# isolator2_0.net
KiCad netlist of a schematic drawn in EAGLE
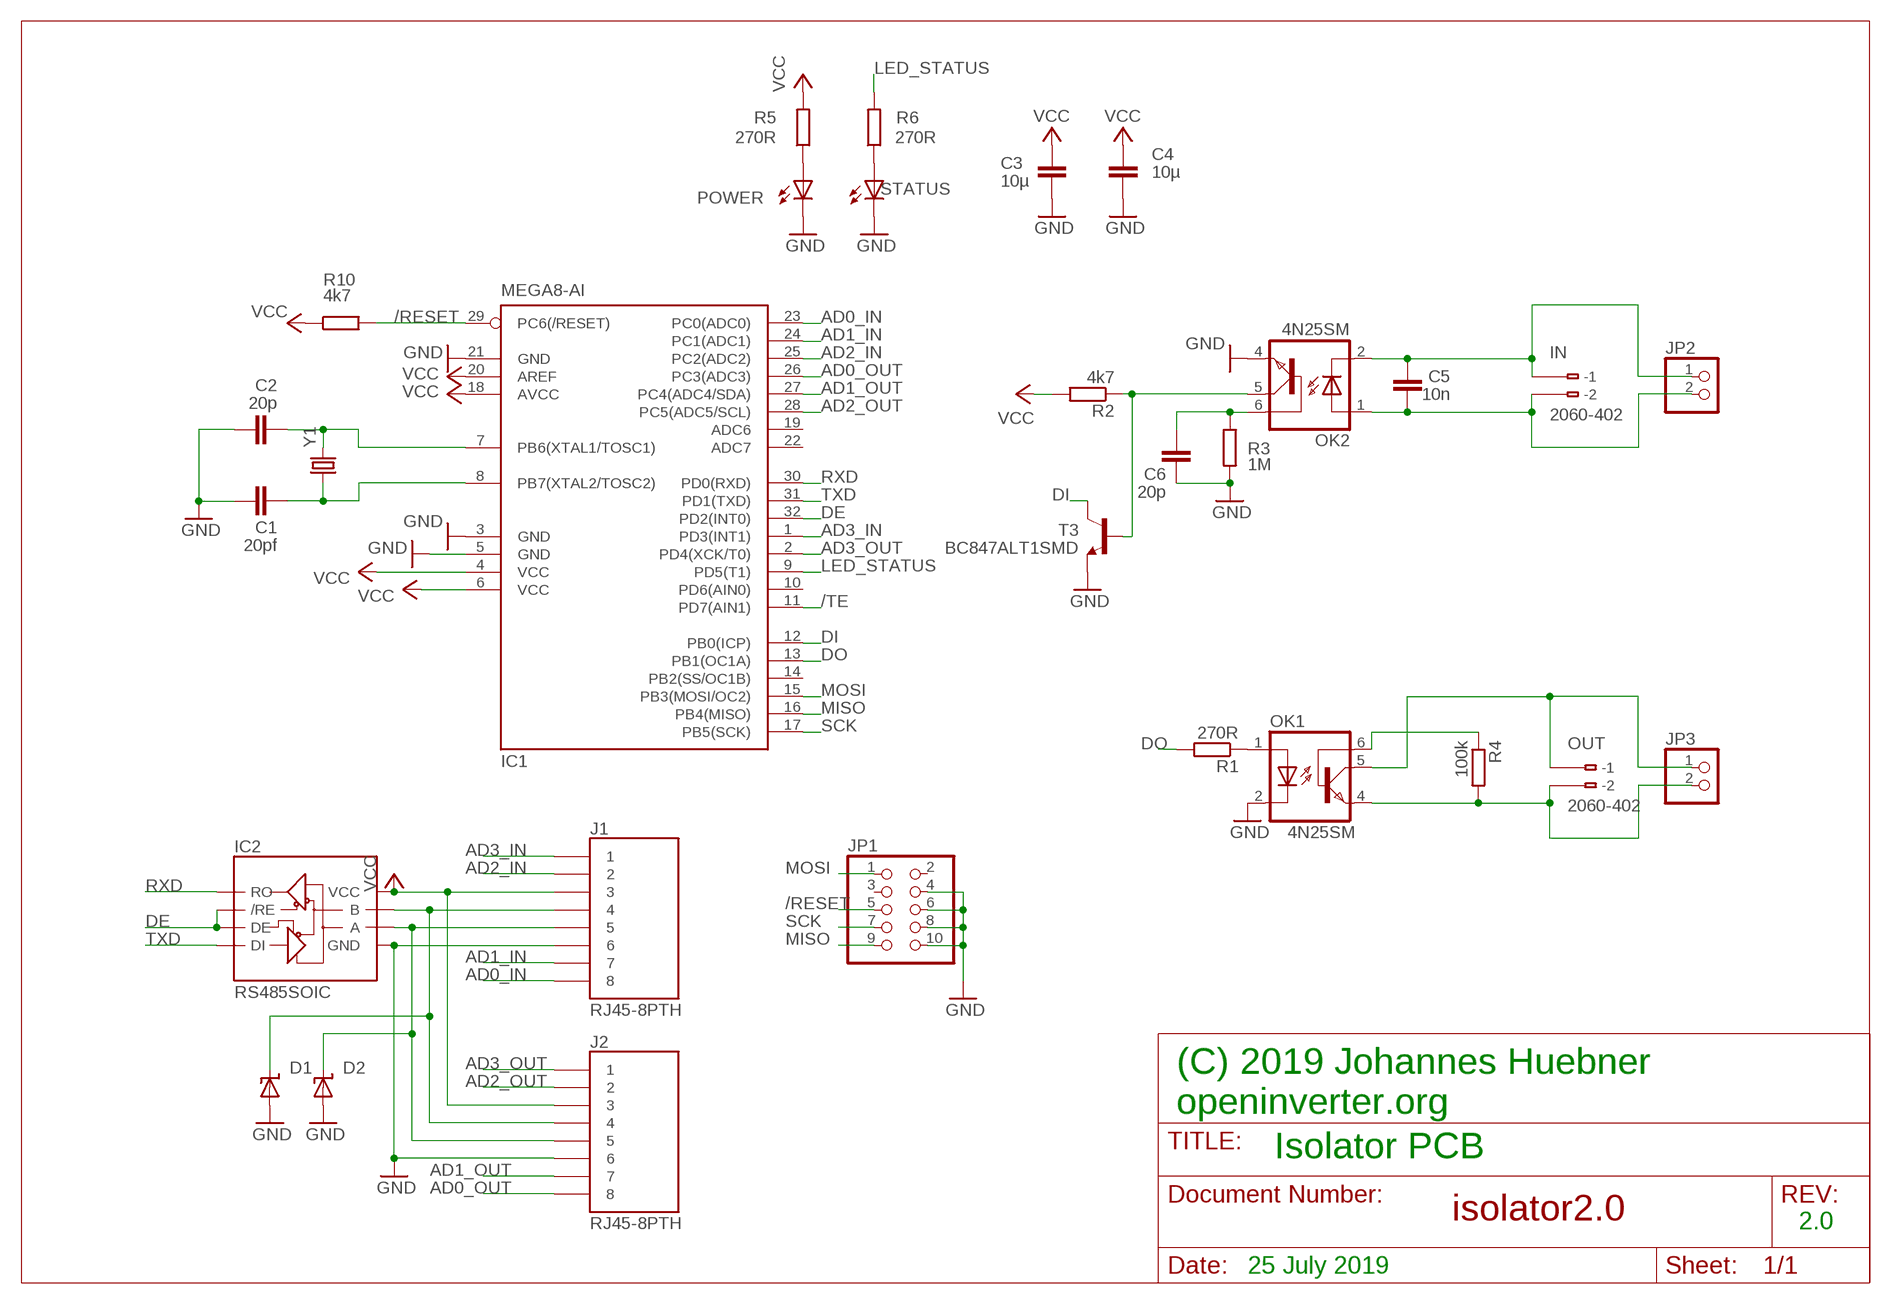
[diagram p0: schematic, sheet 1]

(export (version "E")
  (design (tool "Eeschema 10.0.6"))
  (components
    (comp (ref "C1")
      (value "20pf")
      (footprint "eagle-import:C0805")
      (libsource (lib "eagle-import") (part "C-EUC0805"))
    )
    (comp (ref "C2")
      (value "20p")
      (footprint "eagle-import:C0805")
      (libsource (lib "eagle-import") (part "C-EUC0805"))
    )
    (comp (ref "C3")
      (value "10µ")
      (footprint "eagle-import:C0805")
      (libsource (lib "eagle-import") (part "C-EUC0805"))
    )
    (comp (ref "C4")
      (value "10µ")
      (footprint "eagle-import:C0805")
      (libsource (lib "eagle-import") (part "C-EUC0805"))
    )
    (comp (ref "C5")
      (value "10n")
      (footprint "eagle-import:C0805")
      (libsource (lib "eagle-import") (part "C-EUC0805"))
    )
    (comp (ref "C6")
      (value "20p")
      (footprint "eagle-import:C0805")
      (libsource (lib "eagle-import") (part "C-EUC0805"))
    )
    (comp (ref "D1")
      (value "SUPPRESSOR-SMBJ")
      (footprint "eagle-import:SMBJ")
      (libsource (lib "eagle-import") (part "SUPPRESSOR-SMBJ"))
    )
    (comp (ref "D2")
      (value "SUPPRESSOR-SMBJ")
      (footprint "eagle-import:SMBJ")
      (libsource (lib "eagle-import") (part "SUPPRESSOR-SMBJ"))
    )
    (comp (ref "IC1")
      (value "MEGA8-AI")
      (footprint "eagle-import:TQFP32-08")
      (fields (field (name "MPN") "ATMEGA8-16AU"))
      (libsource (lib "eagle-import") (part "MEGA8-AI"))
    )
    (comp (ref "IC2")
      (value "RS485SOIC")
      (footprint "eagle-import:SO08")
      (libsource (lib "eagle-import") (part "RS485SOIC"))
    )
    (comp (ref "IN")
      (value "2060-402")
      (footprint "eagle-import:2060-402")
      (libsource (lib "eagle-import") (part "2060-402"))
    )
    (comp (ref "J1")
      (value "RJ45-8PTH")
      (footprint "eagle-import:RJ45-8")
      (libsource (lib "eagle-import") (part "RJ45-8PTH"))
    )
    (comp (ref "J2")
      (value "RJ45-8PTH")
      (footprint "eagle-import:RJ45-8")
      (libsource (lib "eagle-import") (part "RJ45-8PTH"))
    )
    (comp (ref "JP1")
      (value "PINHD-2X5")
      (footprint "eagle-import:2X05")
      (libsource (lib "eagle-import") (part "PINHD-2X5"))
    )
    (comp (ref "JP2")
      (value "PINHD-1X2")
      (footprint "eagle-import:1X02")
      (libsource (lib "eagle-import") (part "PINHD-1X2"))
    )
    (comp (ref "JP3")
      (value "PINHD-1X2")
      (footprint "eagle-import:1X02")
      (libsource (lib "eagle-import") (part "PINHD-1X2"))
    )
    (comp (ref "OK1")
      (value "4N25SM")
      (footprint "eagle-import:DIL6-SMD")
      (fields (field (name "MF") "FAIRCHILD SEMICONDUCTOR"))
      (libsource (lib "eagle-import") (part "4N?MS25"))
    )
    (comp (ref "OK2")
      (value "4N25SM")
      (footprint "eagle-import:DIL6-SMD")
      (fields (field (name "MF") "FAIRCHILD SEMICONDUCTOR"))
      (libsource (lib "eagle-import") (part "4N?MS25"))
    )
    (comp (ref "OUT")
      (value "2060-402")
      (footprint "eagle-import:2060-402")
      (libsource (lib "eagle-import") (part "2060-402"))
    )
    (comp (ref "POWER")
      (value "LEDCHIP-LED0805")
      (footprint "eagle-import:CHIP-LED0805")
      (libsource (lib "eagle-import") (part "LEDCHIP-LED0805"))
    )
    (comp (ref "R1")
      (value "270R")
      (footprint "eagle-import:M0805")
      (libsource (lib "eagle-import") (part "R-EU_M0805"))
    )
    (comp (ref "R2")
      (value "4k7")
      (footprint "eagle-import:M0805")
      (libsource (lib "eagle-import") (part "R-EU_M0805"))
    )
    (comp (ref "R3")
      (value "1M")
      (footprint "eagle-import:M0805")
      (libsource (lib "eagle-import") (part "R-EU_M0805"))
    )
    (comp (ref "R4")
      (value "100k")
      (footprint "eagle-import:M0805")
      (libsource (lib "eagle-import") (part "R-EU_M0805"))
    )
    (comp (ref "R5")
      (value "270R")
      (footprint "eagle-import:M0805")
      (libsource (lib "eagle-import") (part "R-EU_M0805"))
    )
    (comp (ref "R6")
      (value "270R")
      (footprint "eagle-import:M0805")
      (libsource (lib "eagle-import") (part "R-EU_M0805"))
    )
    (comp (ref "R10")
      (value "4k7")
      (footprint "eagle-import:M0805")
      (libsource (lib "eagle-import") (part "R-EU_M0805"))
    )
    (comp (ref "STATUS")
      (value "LEDCHIP-LED0805")
      (footprint "eagle-import:CHIP-LED0805")
      (libsource (lib "eagle-import") (part "LEDCHIP-LED0805"))
    )
    (comp (ref "T3")
      (value "BC847ALT1SMD")
      (footprint "eagle-import:SOT23")
      (libsource (lib "eagle-import") (part "BC847SMDALT1"))
    )
    (comp (ref "Y1")
      (value "CRYSTAL10.5X4.8")
      (footprint "eagle-import:CRYSTAL-SMD-10.5X4.8-2PIN")
      (libsource (lib "eagle-import") (part "CRYSTAL10.5X4.8"))
    )
  )
  (nets
    (net (code "1") (name "/AD0_IN") (class "Default")
      (node (ref "IC1") (pin "23") (pinfunction "PC0(ADC0)_23") (pintype "bidirectional"))
      (node (ref "J1") (pin "8") (pinfunction "8_8") (pintype "bidirectional"))
    )
    (net (code "2") (name "/AD0_OUT") (class "Default")
      (node (ref "IC1") (pin "26") (pinfunction "PC3(ADC3)_26") (pintype "bidirectional"))
      (node (ref "J2") (pin "8") (pinfunction "8_8") (pintype "bidirectional"))
    )
    (net (code "3") (name "/AD1_IN") (class "Default")
      (node (ref "IC1") (pin "24") (pinfunction "PC1(ADC1)_24") (pintype "bidirectional"))
      (node (ref "J1") (pin "7") (pinfunction "7_7") (pintype "bidirectional"))
    )
    (net (code "4") (name "/AD1_OUT") (class "Default")
      (node (ref "IC1") (pin "27") (pinfunction "PC4(ADC4/SDA)_27") (pintype "bidirectional"))
      (node (ref "J2") (pin "7") (pinfunction "7_7") (pintype "bidirectional"))
    )
    (net (code "5") (name "/AD2_IN") (class "Default")
      (node (ref "IC1") (pin "25") (pinfunction "PC2(ADC2)_25") (pintype "bidirectional"))
      (node (ref "J1") (pin "2") (pinfunction "2_2") (pintype "bidirectional"))
    )
    (net (code "6") (name "/AD2_OUT") (class "Default")
      (node (ref "IC1") (pin "28") (pinfunction "PC5(ADC5/SCL)_28") (pintype "bidirectional"))
      (node (ref "J2") (pin "2") (pinfunction "2_2") (pintype "bidirectional"))
    )
    (net (code "7") (name "/AD3_IN") (class "Default")
      (node (ref "IC1") (pin "1") (pinfunction "PD3(INT1)_1") (pintype "bidirectional"))
      (node (ref "J1") (pin "1") (pinfunction "1_1") (pintype "bidirectional"))
    )
    (net (code "8") (name "/AD3_OUT") (class "Default")
      (node (ref "IC1") (pin "2") (pinfunction "PD4(XCK/T0)_2") (pintype "bidirectional"))
      (node (ref "J2") (pin "1") (pinfunction "1_1") (pintype "bidirectional"))
    )
    (net (code "9") (name "/DE") (class "Default")
      (node (ref "IC1") (pin "32") (pinfunction "PD2(INT0)_32") (pintype "bidirectional"))
      (node (ref "IC2") (pin "2") (pinfunction "/RE_2") (pintype "bidirectional"))
      (node (ref "IC2") (pin "3") (pinfunction "DE_3") (pintype "bidirectional"))
    )
    (net (code "10") (name "/DI") (class "Default")
      (node (ref "IC1") (pin "12") (pinfunction "PB0(ICP)_12") (pintype "bidirectional"))
      (node (ref "T3") (pin "3") (pinfunction "C_3") (pintype "passive"))
    )
    (net (code "11") (name "/DO") (class "Default")
      (node (ref "IC1") (pin "13") (pinfunction "PB1(OC1A)_13") (pintype "bidirectional"))
      (node (ref "R1") (pin "2") (pinfunction "2_2") (pintype "passive"))
    )
    (net (code "12") (name "/LED_STATUS") (class "Default")
      (node (ref "IC1") (pin "9") (pinfunction "PD5(T1)_9") (pintype "bidirectional"))
      (node (ref "R6") (pin "2") (pinfunction "2_2") (pintype "passive"))
    )
    (net (code "13") (name "/MISO") (class "Default")
      (node (ref "IC1") (pin "16") (pinfunction "PB4(MISO)_16") (pintype "bidirectional"))
      (node (ref "JP1") (pin "9") (pinfunction "9_9") (pintype "passive"))
    )
    (net (code "14") (name "/MOSI") (class "Default")
      (node (ref "IC1") (pin "15") (pinfunction "PB3(MOSI/OC2)_15") (pintype "bidirectional"))
      (node (ref "JP1") (pin "1") (pinfunction "1_1") (pintype "passive"))
    )
    (net (code "15") (name "/RXD") (class "Default")
      (node (ref "IC1") (pin "30") (pinfunction "PD0(RXD)_30") (pintype "bidirectional"))
      (node (ref "IC2") (pin "1") (pinfunction "RO_1") (pintype "bidirectional"))
    )
    (net (code "16") (name "/SCK") (class "Default")
      (node (ref "IC1") (pin "17") (pinfunction "PB5(SCK)_17") (pintype "bidirectional"))
      (node (ref "JP1") (pin "7") (pinfunction "7_7") (pintype "passive"))
    )
    (net (code "17") (name "/TXD") (class "Default")
      (node (ref "IC1") (pin "31") (pinfunction "PD1(TXD)_31") (pintype "bidirectional"))
      (node (ref "IC2") (pin "4") (pinfunction "DI_4") (pintype "bidirectional"))
    )
    (net (code "18") (name "/{slash}RESET") (class "Default")
      (node (ref "IC1") (pin "29") (pinfunction "PC6(/RESET)_29") (pintype "bidirectional"))
      (node (ref "JP1") (pin "5") (pinfunction "5_5") (pintype "passive"))
      (node (ref "R10") (pin "2") (pinfunction "2_2") (pintype "passive"))
    )
    (net (code "19") (name "/{slash}TE") (class "Default")
      (node (ref "IC1") (pin "11") (pinfunction "PD7(AIN1)_11") (pintype "bidirectional"))
    )
    (net (code "20") (name "GND") (class "Default")
      (node (ref "C1") (pin "1") (pinfunction "1_1") (pintype "passive"))
      (node (ref "C2") (pin "1") (pinfunction "1_1") (pintype "passive"))
      (node (ref "C3") (pin "2") (pinfunction "2_2") (pintype "passive"))
      (node (ref "C4") (pin "2") (pinfunction "2_2") (pintype "passive"))
      (node (ref "C6") (pin "1") (pinfunction "1_1") (pintype "passive"))
      (node (ref "D1") (pin "A") (pinfunction "A_A") (pintype "passive"))
      (node (ref "D2") (pin "A") (pinfunction "A_A") (pintype "passive"))
      (node (ref "IC1") (pin "21") (pinfunction "GND_21") (pintype "power_in"))
      (node (ref "IC1") (pin "3") (pinfunction "GND_3") (pintype "power_in"))
      (node (ref "IC1") (pin "5") (pinfunction "GND_5") (pintype "power_in"))
      (node (ref "IC2") (pin "5") (pinfunction "GND_5") (pintype "bidirectional"))
      (node (ref "J1") (pin "6") (pinfunction "6_6") (pintype "bidirectional"))
      (node (ref "J2") (pin "6") (pinfunction "6_6") (pintype "bidirectional"))
      (node (ref "JP1") (pin "10") (pinfunction "10_10") (pintype "passive"))
      (node (ref "JP1") (pin "4") (pinfunction "4_4") (pintype "passive"))
      (node (ref "JP1") (pin "6") (pinfunction "6_6") (pintype "passive"))
      (node (ref "JP1") (pin "8") (pinfunction "8_8") (pintype "passive"))
      (node (ref "OK1") (pin "2") (pinfunction "C_2") (pintype "passive"))
      (node (ref "OK2") (pin "4") (pinfunction "EMI_4") (pintype "passive"))
      (node (ref "POWER") (pin "C") (pinfunction "C_C") (pintype "passive"))
      (node (ref "R3") (pin "2") (pinfunction "2_2") (pintype "passive"))
      (node (ref "STATUS") (pin "C") (pinfunction "C_C") (pintype "passive"))
      (node (ref "T3") (pin "2") (pinfunction "E_2") (pintype "passive"))
    )
    (net (code "21") (name "Net-(IC1-PB6(XTAL1{slash}TOSC1))") (class "Default")
      (node (ref "C2") (pin "2") (pinfunction "2_2") (pintype "passive"))
      (node (ref "IC1") (pin "7") (pinfunction "PB6(XTAL1/TOSC1)_7") (pintype "bidirectional"))
      (node (ref "Y1") (pin "P$2") (pinfunction "2_P$2") (pintype "passive"))
    )
    (net (code "22") (name "Net-(IC1-PB7(XTAL2{slash}TOSC2))") (class "Default")
      (node (ref "C1") (pin "2") (pinfunction "2_2") (pintype "passive"))
      (node (ref "IC1") (pin "8") (pinfunction "PB7(XTAL2/TOSC2)_8") (pintype "bidirectional"))
      (node (ref "Y1") (pin "P$1") (pinfunction "1_P$1") (pintype "passive"))
    )
    (net (code "23") (name "Net-(IC2-A)") (class "Default")
      (node (ref "D2") (pin "C") (pinfunction "C_C") (pintype "passive"))
      (node (ref "IC2") (pin "6") (pinfunction "A_6") (pintype "bidirectional"))
      (node (ref "J1") (pin "5") (pinfunction "5_5") (pintype "bidirectional"))
      (node (ref "J2") (pin "5") (pinfunction "5_5") (pintype "bidirectional"))
    )
    (net (code "24") (name "Net-(IC2-B)") (class "Default")
      (node (ref "D1") (pin "C") (pinfunction "C_C") (pintype "passive"))
      (node (ref "IC2") (pin "7") (pinfunction "B_7") (pintype "bidirectional"))
      (node (ref "J1") (pin "4") (pinfunction "4_4") (pintype "bidirectional"))
      (node (ref "J2") (pin "4") (pinfunction "4_4") (pintype "bidirectional"))
    )
    (net (code "25") (name "Net-(IN-B-1)") (class "Default")
      (node (ref "C5") (pin "2") (pinfunction "2_2") (pintype "passive"))
      (node (ref "IN") (pin "P21") (pinfunction "B-1_P21") (pintype "passive"))
      (node (ref "JP2") (pin "1") (pinfunction "1_1") (pintype "passive"))
      (node (ref "OK2") (pin "2") (pinfunction "C_2") (pintype "passive"))
    )
    (net (code "26") (name "Net-(IN-B-2)") (class "Default")
      (node (ref "C5") (pin "1") (pinfunction "1_1") (pintype "passive"))
      (node (ref "IN") (pin "P22") (pinfunction "B-2_P22") (pintype "passive"))
      (node (ref "JP2") (pin "2") (pinfunction "2_2") (pintype "passive"))
      (node (ref "OK2") (pin "1") (pinfunction "A_1") (pintype "passive"))
    )
    (net (code "27") (name "Net-(OK1-A)") (class "Default")
      (node (ref "OK1") (pin "1") (pinfunction "A_1") (pintype "passive"))
      (node (ref "R1") (pin "1") (pinfunction "1_1") (pintype "passive"))
    )
    (net (code "28") (name "Net-(OK1-BAS)") (class "Default")
      (node (ref "OK1") (pin "6") (pinfunction "BAS_6") (pintype "passive"))
      (node (ref "R4") (pin "1") (pinfunction "1_1") (pintype "passive"))
    )
    (net (code "29") (name "Net-(OK1-COL)") (class "Default")
      (node (ref "JP3") (pin "1") (pinfunction "1_1") (pintype "passive"))
      (node (ref "OK1") (pin "5") (pinfunction "COL_5") (pintype "passive"))
      (node (ref "OUT") (pin "P21") (pinfunction "B-1_P21") (pintype "passive"))
    )
    (net (code "30") (name "Net-(OK1-EMI)") (class "Default")
      (node (ref "JP3") (pin "2") (pinfunction "2_2") (pintype "passive"))
      (node (ref "OK1") (pin "4") (pinfunction "EMI_4") (pintype "passive"))
      (node (ref "OUT") (pin "P22") (pinfunction "B-2_P22") (pintype "passive"))
      (node (ref "R4") (pin "2") (pinfunction "2_2") (pintype "passive"))
    )
    (net (code "31") (name "Net-(OK2-BAS)") (class "Default")
      (node (ref "C6") (pin "2") (pinfunction "2_2") (pintype "passive"))
      (node (ref "OK2") (pin "6") (pinfunction "BAS_6") (pintype "passive"))
      (node (ref "R3") (pin "1") (pinfunction "1_1") (pintype "passive"))
    )
    (net (code "32") (name "Net-(OK2-COL)") (class "Default")
      (node (ref "OK2") (pin "5") (pinfunction "COL_5") (pintype "passive"))
      (node (ref "R2") (pin "1") (pinfunction "1_1") (pintype "passive"))
      (node (ref "T3") (pin "1") (pinfunction "B_1") (pintype "passive"))
    )
    (net (code "33") (name "Net-(POWER-PadA)") (class "Default")
      (node (ref "POWER") (pin "A") (pinfunction "A_A") (pintype "passive"))
      (node (ref "R5") (pin "1") (pinfunction "1_1") (pintype "passive"))
    )
    (net (code "34") (name "Net-(R6-Pad1)") (class "Default")
      (node (ref "R6") (pin "1") (pinfunction "1_1") (pintype "passive"))
      (node (ref "STATUS") (pin "A") (pinfunction "A_A") (pintype "passive"))
    )
    (net (code "35") (name "VCC") (class "Default")
      (node (ref "C3") (pin "1") (pinfunction "1_1") (pintype "passive"))
      (node (ref "C4") (pin "1") (pinfunction "1_1") (pintype "passive"))
      (node (ref "IC1") (pin "18") (pinfunction "AVCC_18") (pintype "power_in"))
      (node (ref "IC1") (pin "20") (pinfunction "AREF_20") (pintype "passive"))
      (node (ref "IC1") (pin "4") (pinfunction "VCC_4") (pintype "power_in"))
      (node (ref "IC1") (pin "6") (pinfunction "VCC_6") (pintype "power_in"))
      (node (ref "IC2") (pin "8") (pinfunction "VCC_8") (pintype "bidirectional"))
      (node (ref "J1") (pin "3") (pinfunction "3_3") (pintype "bidirectional"))
      (node (ref "J2") (pin "3") (pinfunction "3_3") (pintype "bidirectional"))
      (node (ref "R10") (pin "1") (pinfunction "1_1") (pintype "passive"))
      (node (ref "R2") (pin "2") (pinfunction "2_2") (pintype "passive"))
      (node (ref "R5") (pin "2") (pinfunction "2_2") (pintype "passive"))
    )
    (net (code "36") (name "unconnected-(IC1-ADC6-Pad19)") (class "Default")
      (node (ref "IC1") (pin "19") (pinfunction "ADC6_19") (pintype "bidirectional"))
    )
    (net (code "37") (name "unconnected-(IC1-ADC7-Pad22)") (class "Default")
      (node (ref "IC1") (pin "22") (pinfunction "ADC7_22") (pintype "bidirectional"))
    )
    (net (code "38") (name "unconnected-(IC1-PB2(SS{slash}OC1B)-Pad14)") (class "Default")
      (node (ref "IC1") (pin "14") (pinfunction "PB2(SS/OC1B)_14") (pintype "bidirectional"))
    )
    (net (code "39") (name "unconnected-(IC1-PD6(AIN0)-Pad10)") (class "Default")
      (node (ref "IC1") (pin "10") (pinfunction "PD6(AIN0)_10") (pintype "bidirectional"))
    )
    (net (code "40") (name "unconnected-(IN--1-PadP1.1)") (class "Default")
      (node (ref "IN") (pin "P1.1") (pinfunction "-1_P1.1") (pintype "passive"))
    )
    (net (code "41") (name "unconnected-(IN--2-PadP1.2)") (class "Default")
      (node (ref "IN") (pin "P1.2") (pinfunction "-2_P1.2") (pintype "passive"))
    )
    (net (code "42") (name "unconnected-(JP1-Pad2)") (class "Default")
      (node (ref "JP1") (pin "2") (pinfunction "2_2") (pintype "passive"))
    )
    (net (code "43") (name "unconnected-(JP1-Pad3)") (class "Default")
      (node (ref "JP1") (pin "3") (pinfunction "3_3") (pintype "passive"))
    )
    (net (code "44") (name "unconnected-(OUT--1-PadP1.1)") (class "Default")
      (node (ref "OUT") (pin "P1.1") (pinfunction "-1_P1.1") (pintype "passive"))
    )
    (net (code "45") (name "unconnected-(OUT--2-PadP1.2)") (class "Default")
      (node (ref "OUT") (pin "P1.2") (pinfunction "-2_P1.2") (pintype "passive"))
    )
  )
)
